# ReuseBlock_esp32_on_connector_2024-12-01.net
KiCad netlist of a schematic drawn in EasyEDA Pro
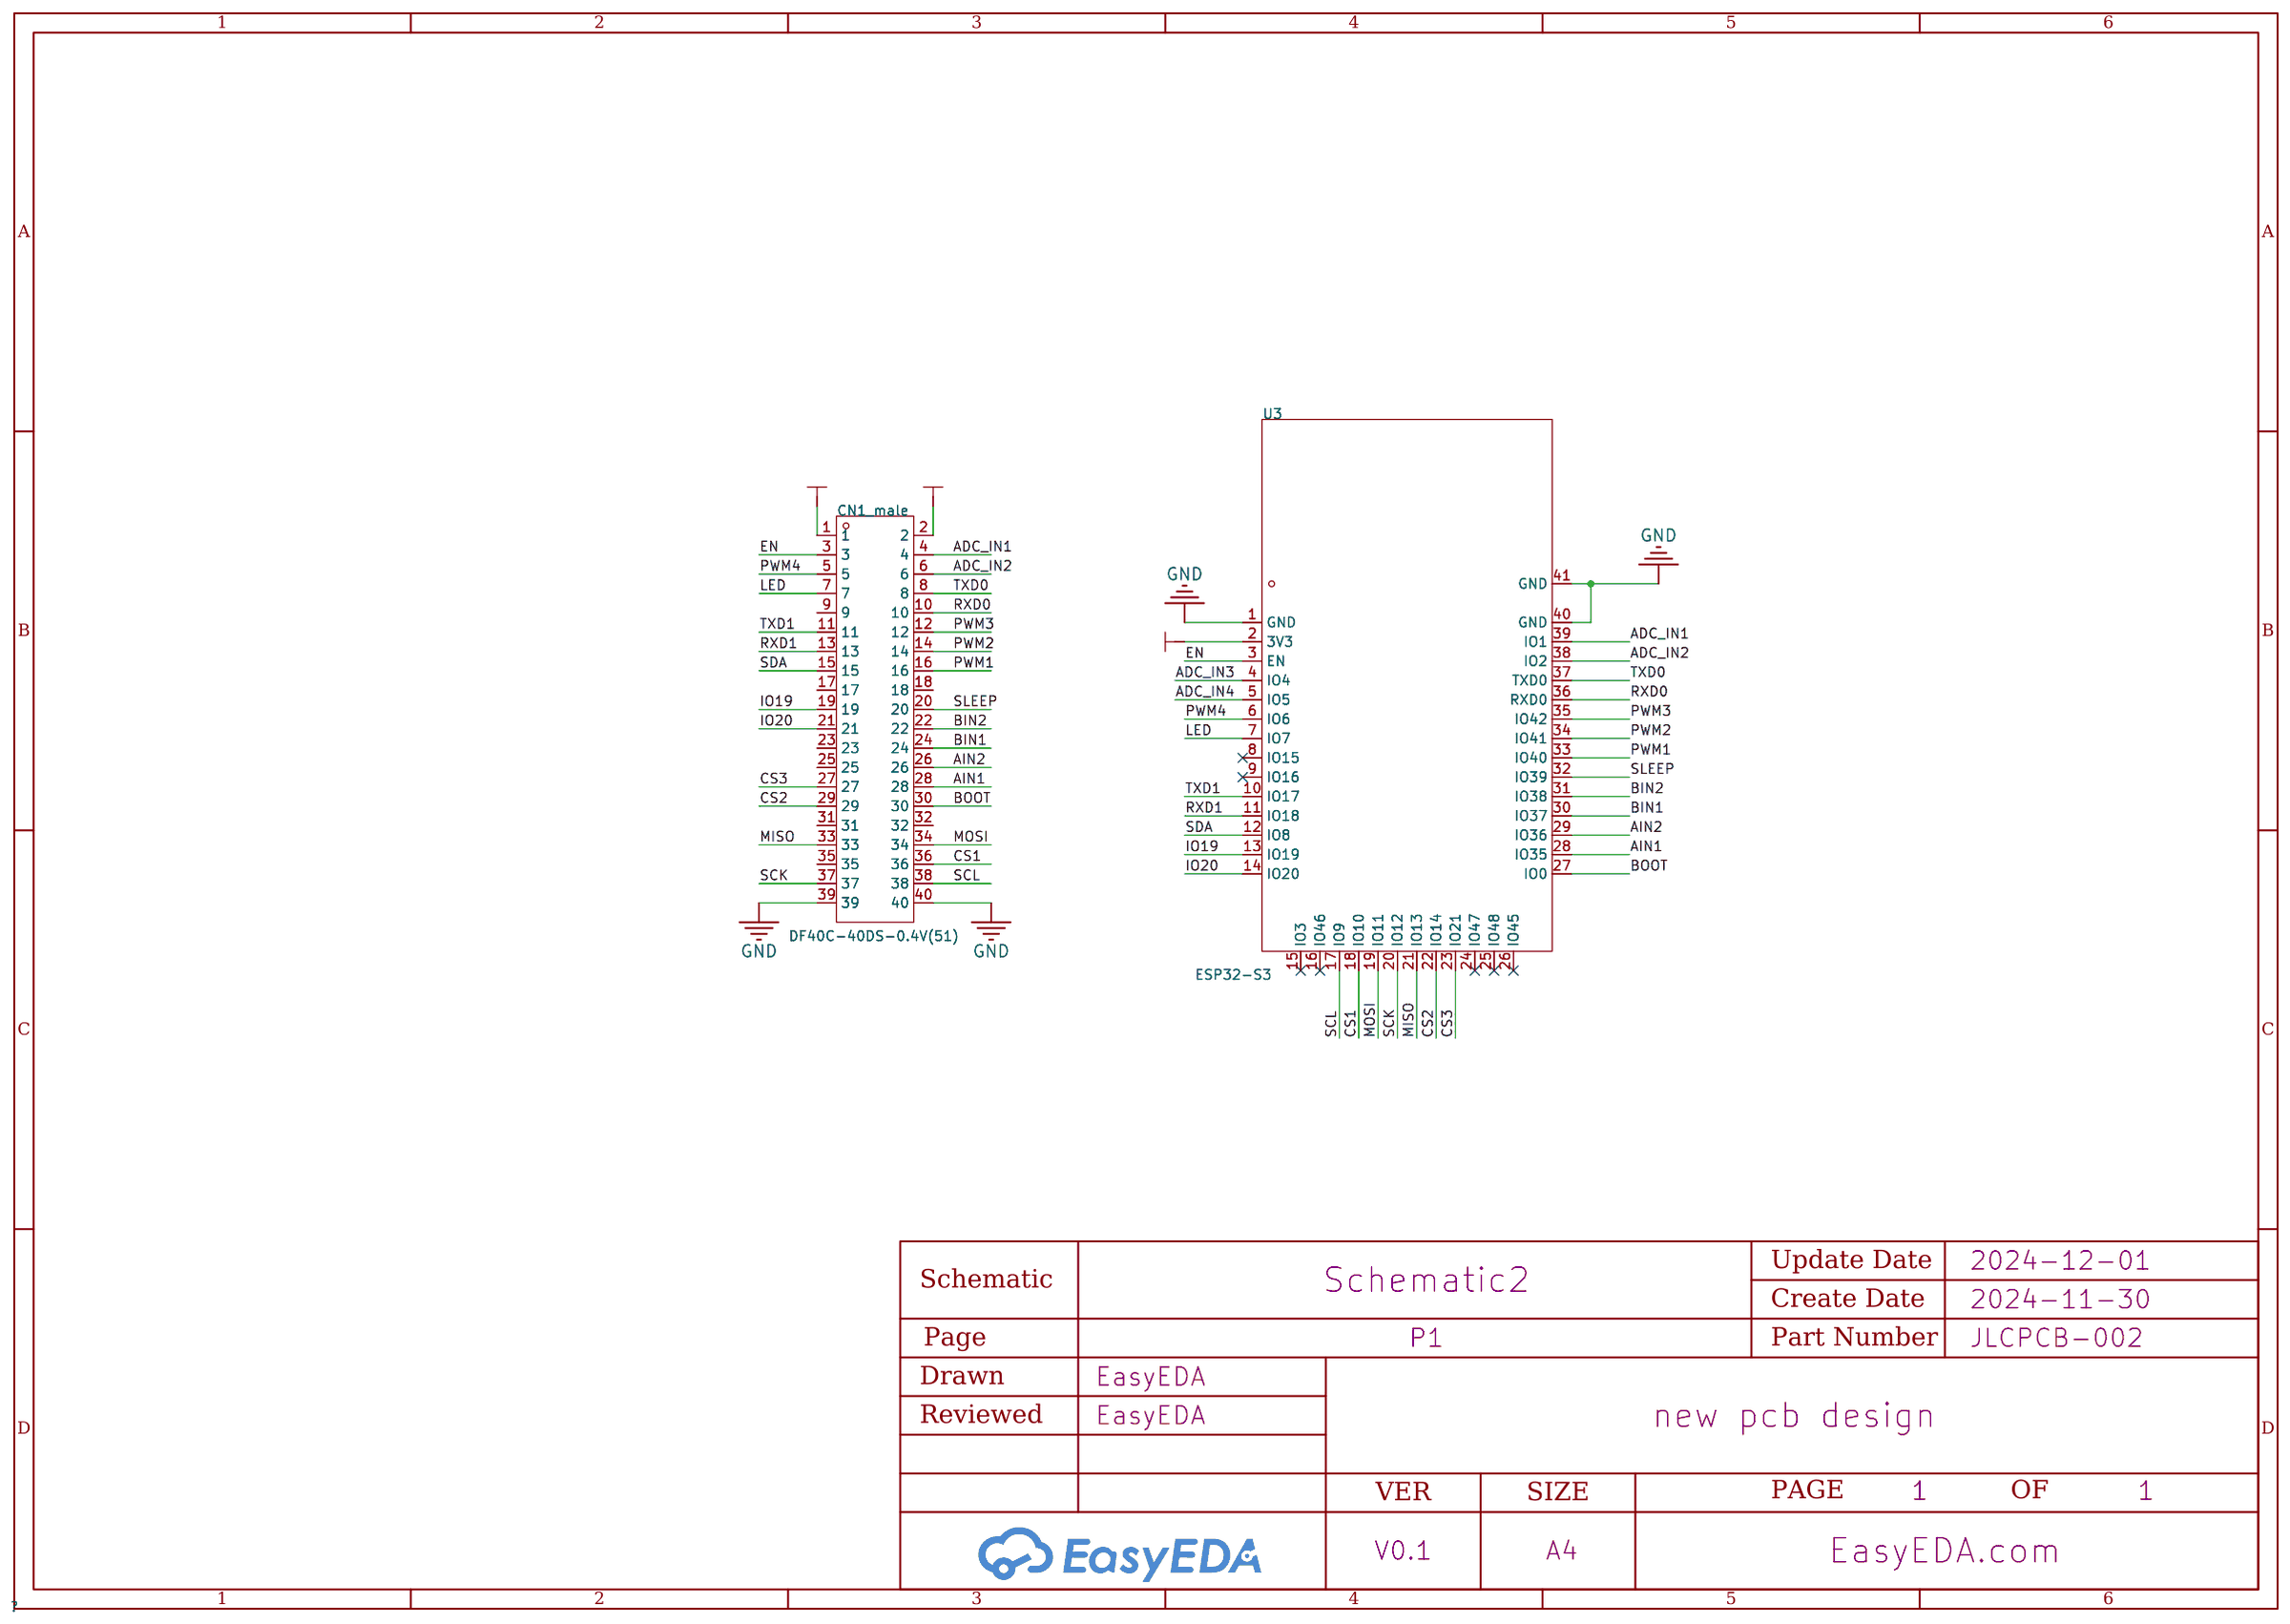
[diagram p0: schematic sheet]

(export (version "E")
  (design (tool "Eeschema 10.0.6"))
  (components
    (comp (ref "CN1_male")
      (value "DF40C-40DS-0.4V(51)")
      (footprint "easyedapro:CONN-SMD_DF40C-40DS-0.4V51")
      (fields (field (name "Manufacturer") "HRS(广濑)"))
      (libsource (lib "easyedapro") (part "DF40C-40DS-0.4V(51)"))
    )
    (comp (ref "U3")
      (value "ESP32-S3")
      (footprint "easyedapro:WIRELM-SMD_ESP32-S3-WROOM-1")
      (description "Core Processor:ESP32-S3 Chip Support Interface:I2C；GPIO；SPI；PWM；ADC；UART；USB；I2S Frequency:2.4GHz")
      (fields
        (field (name "Manufacturer Part") "ESP32-S3-WROOM-1-N8R2")
        (field (name "Manufacturer") "ESPRESSIF(乐鑫)")
      )
      (libsource (lib "easyedapro") (part "ESP32-S3-WROOM-1(N8R2)"))
    )
  )
  (nets
    (net (code "1") (name "/ADC_IN1") (class "Default")
      (node (ref "CN1_male") (pin "4") (pinfunction "4_4") (pintype "unspecified"))
      (node (ref "U3") (pin "39") (pinfunction "IO1_39") (pintype "unspecified"))
    )
    (net (code "2") (name "/ADC_IN2") (class "Default")
      (node (ref "CN1_male") (pin "6") (pinfunction "6_6") (pintype "unspecified"))
      (node (ref "U3") (pin "38") (pinfunction "IO2_38") (pintype "unspecified"))
    )
    (net (code "3") (name "/ADC_IN3") (class "Default")
      (node (ref "U3") (pin "4") (pinfunction "IO4_4") (pintype "unspecified"))
    )
    (net (code "4") (name "/ADC_IN4") (class "Default")
      (node (ref "U3") (pin "5") (pinfunction "IO5_5") (pintype "unspecified"))
    )
    (net (code "5") (name "/AIN1") (class "Default")
      (node (ref "CN1_male") (pin "28") (pinfunction "28_28") (pintype "unspecified"))
      (node (ref "U3") (pin "28") (pinfunction "IO35_28") (pintype "unspecified"))
    )
    (net (code "6") (name "/AIN2") (class "Default")
      (node (ref "CN1_male") (pin "26") (pinfunction "26_26") (pintype "unspecified"))
      (node (ref "U3") (pin "29") (pinfunction "IO36_29") (pintype "unspecified"))
    )
    (net (code "7") (name "/BIN1") (class "Default")
      (node (ref "CN1_male") (pin "24") (pinfunction "24_24") (pintype "unspecified"))
      (node (ref "U3") (pin "30") (pinfunction "IO37_30") (pintype "unspecified"))
    )
    (net (code "8") (name "/BIN2") (class "Default")
      (node (ref "CN1_male") (pin "22") (pinfunction "22_22") (pintype "unspecified"))
      (node (ref "U3") (pin "31") (pinfunction "IO38_31") (pintype "unspecified"))
    )
    (net (code "9") (name "/BOOT") (class "Default")
      (node (ref "CN1_male") (pin "30") (pinfunction "30_30") (pintype "unspecified"))
      (node (ref "U3") (pin "27") (pinfunction "IO0_27") (pintype "unspecified"))
    )
    (net (code "10") (name "/CS1") (class "Default")
      (node (ref "CN1_male") (pin "36") (pinfunction "36_36") (pintype "unspecified"))
      (node (ref "U3") (pin "18") (pinfunction "IO10_18") (pintype "unspecified"))
    )
    (net (code "11") (name "/CS2") (class "Default")
      (node (ref "CN1_male") (pin "29") (pinfunction "29_29") (pintype "unspecified"))
      (node (ref "U3") (pin "22") (pinfunction "IO14_22") (pintype "unspecified"))
    )
    (net (code "12") (name "/CS3") (class "Default")
      (node (ref "CN1_male") (pin "27") (pinfunction "27_27") (pintype "unspecified"))
      (node (ref "U3") (pin "23") (pinfunction "IO21_23") (pintype "unspecified"))
    )
    (net (code "13") (name "/EN") (class "Default")
      (node (ref "CN1_male") (pin "3") (pinfunction "3_3") (pintype "unspecified"))
      (node (ref "U3") (pin "3") (pinfunction "EN_3") (pintype "unspecified"))
    )
    (net (code "14") (name "/IO19") (class "Default")
      (node (ref "CN1_male") (pin "19") (pinfunction "19_19") (pintype "unspecified"))
      (node (ref "U3") (pin "13") (pinfunction "IO19_13") (pintype "unspecified"))
    )
    (net (code "15") (name "/IO20") (class "Default")
      (node (ref "CN1_male") (pin "21") (pinfunction "21_21") (pintype "unspecified"))
      (node (ref "U3") (pin "14") (pinfunction "IO20_14") (pintype "unspecified"))
    )
    (net (code "16") (name "/LED") (class "Default")
      (node (ref "CN1_male") (pin "7") (pinfunction "7_7") (pintype "unspecified"))
      (node (ref "U3") (pin "7") (pinfunction "IO7_7") (pintype "unspecified"))
    )
    (net (code "17") (name "/MISO") (class "Default")
      (node (ref "CN1_male") (pin "33") (pinfunction "33_33") (pintype "unspecified"))
      (node (ref "U3") (pin "21") (pinfunction "IO13_21") (pintype "unspecified"))
    )
    (net (code "18") (name "/MOSI") (class "Default")
      (node (ref "CN1_male") (pin "34") (pinfunction "34_34") (pintype "unspecified"))
      (node (ref "U3") (pin "19") (pinfunction "IO11_19") (pintype "unspecified"))
    )
    (net (code "19") (name "/PWM1") (class "Default")
      (node (ref "CN1_male") (pin "16") (pinfunction "16_16") (pintype "unspecified"))
      (node (ref "U3") (pin "33") (pinfunction "IO40_33") (pintype "unspecified"))
    )
    (net (code "20") (name "/PWM2") (class "Default")
      (node (ref "CN1_male") (pin "14") (pinfunction "14_14") (pintype "unspecified"))
      (node (ref "U3") (pin "34") (pinfunction "IO41_34") (pintype "unspecified"))
    )
    (net (code "21") (name "/PWM3") (class "Default")
      (node (ref "CN1_male") (pin "12") (pinfunction "12_12") (pintype "unspecified"))
      (node (ref "U3") (pin "35") (pinfunction "IO42_35") (pintype "unspecified"))
    )
    (net (code "22") (name "/PWM4") (class "Default")
      (node (ref "CN1_male") (pin "5") (pinfunction "5_5") (pintype "unspecified"))
      (node (ref "U3") (pin "6") (pinfunction "IO6_6") (pintype "unspecified"))
    )
    (net (code "23") (name "/RXD0") (class "Default")
      (node (ref "CN1_male") (pin "10") (pinfunction "10_10") (pintype "unspecified"))
      (node (ref "U3") (pin "36") (pinfunction "RXD0_36") (pintype "unspecified"))
    )
    (net (code "24") (name "/RXD1") (class "Default")
      (node (ref "CN1_male") (pin "13") (pinfunction "13_13") (pintype "unspecified"))
      (node (ref "U3") (pin "11") (pinfunction "IO18_11") (pintype "unspecified"))
    )
    (net (code "25") (name "/SCK") (class "Default")
      (node (ref "CN1_male") (pin "37") (pinfunction "37_37") (pintype "unspecified"))
      (node (ref "U3") (pin "20") (pinfunction "IO12_20") (pintype "unspecified"))
    )
    (net (code "26") (name "/SCL") (class "Default")
      (node (ref "CN1_male") (pin "38") (pinfunction "38_38") (pintype "unspecified"))
      (node (ref "U3") (pin "17") (pinfunction "IO9_17") (pintype "unspecified"))
    )
    (net (code "27") (name "/SDA") (class "Default")
      (node (ref "CN1_male") (pin "15") (pinfunction "15_15") (pintype "unspecified"))
      (node (ref "U3") (pin "12") (pinfunction "IO8_12") (pintype "unspecified"))
    )
    (net (code "28") (name "/SLEEP") (class "Default")
      (node (ref "CN1_male") (pin "20") (pinfunction "20_20") (pintype "unspecified"))
      (node (ref "U3") (pin "32") (pinfunction "IO39_32") (pintype "unspecified"))
    )
    (net (code "29") (name "/TXD0") (class "Default")
      (node (ref "CN1_male") (pin "8") (pinfunction "8_8") (pintype "unspecified"))
      (node (ref "U3") (pin "37") (pinfunction "TXD0_37") (pintype "unspecified"))
    )
    (net (code "30") (name "/TXD1") (class "Default")
      (node (ref "CN1_male") (pin "11") (pinfunction "11_11") (pintype "unspecified"))
      (node (ref "U3") (pin "10") (pinfunction "IO17_10") (pintype "unspecified"))
    )
    (net (code "31") (name "GND") (class "Default")
      (node (ref "CN1_male") (pin "39") (pinfunction "39_39") (pintype "unspecified"))
      (node (ref "CN1_male") (pin "40") (pinfunction "40_40") (pintype "unspecified"))
      (node (ref "U3") (pin "1") (pinfunction "GND_1") (pintype "unspecified"))
      (node (ref "U3") (pin "40") (pinfunction "GND_40") (pintype "unspecified"))
      (node (ref "U3") (pin "41") (pinfunction "GND_41") (pintype "unspecified"))
    )
    (net (code "32") (name "VCC_3V3") (class "Default")
      (node (ref "CN1_male") (pin "1") (pinfunction "1_1") (pintype "unspecified"))
      (node (ref "CN1_male") (pin "2") (pinfunction "2_2") (pintype "unspecified"))
      (node (ref "U3") (pin "2") (pinfunction "3V3_2") (pintype "unspecified"))
    )
    (net (code "33") (name "unconnected-(CN1_male-Pad9)") (class "Default")
      (node (ref "CN1_male") (pin "9") (pinfunction "9_9") (pintype "unspecified"))
    )
    (net (code "34") (name "unconnected-(CN1_male-Pad17)") (class "Default")
      (node (ref "CN1_male") (pin "17") (pinfunction "17_17") (pintype "unspecified"))
    )
    (net (code "35") (name "unconnected-(CN1_male-Pad18)") (class "Default")
      (node (ref "CN1_male") (pin "18") (pinfunction "18_18") (pintype "unspecified"))
    )
    (net (code "36") (name "unconnected-(CN1_male-Pad23)") (class "Default")
      (node (ref "CN1_male") (pin "23") (pinfunction "23_23") (pintype "unspecified"))
    )
    (net (code "37") (name "unconnected-(CN1_male-Pad25)") (class "Default")
      (node (ref "CN1_male") (pin "25") (pinfunction "25_25") (pintype "unspecified"))
    )
    (net (code "38") (name "unconnected-(CN1_male-Pad31)") (class "Default")
      (node (ref "CN1_male") (pin "31") (pinfunction "31_31") (pintype "unspecified"))
    )
    (net (code "39") (name "unconnected-(CN1_male-Pad32)") (class "Default")
      (node (ref "CN1_male") (pin "32") (pinfunction "32_32") (pintype "unspecified"))
    )
    (net (code "40") (name "unconnected-(CN1_male-Pad35)") (class "Default")
      (node (ref "CN1_male") (pin "35") (pinfunction "35_35") (pintype "unspecified"))
    )
    (net (code "41") (name "unconnected-(U3-IO3-Pad15)") (class "Default")
      (node (ref "U3") (pin "15") (pinfunction "IO3_15") (pintype "unspecified+no_connect"))
    )
    (net (code "42") (name "unconnected-(U3-IO15-Pad8)") (class "Default")
      (node (ref "U3") (pin "8") (pinfunction "IO15_8") (pintype "unspecified+no_connect"))
    )
    (net (code "43") (name "unconnected-(U3-IO16-Pad9)") (class "Default")
      (node (ref "U3") (pin "9") (pinfunction "IO16_9") (pintype "unspecified+no_connect"))
    )
    (net (code "44") (name "unconnected-(U3-IO45-Pad26)") (class "Default")
      (node (ref "U3") (pin "26") (pinfunction "IO45_26") (pintype "unspecified+no_connect"))
    )
    (net (code "45") (name "unconnected-(U3-IO46-Pad16)") (class "Default")
      (node (ref "U3") (pin "16") (pinfunction "IO46_16") (pintype "unspecified+no_connect"))
    )
    (net (code "46") (name "unconnected-(U3-IO47-Pad24)") (class "Default")
      (node (ref "U3") (pin "24") (pinfunction "IO47_24") (pintype "unspecified+no_connect"))
    )
    (net (code "47") (name "unconnected-(U3-IO48-Pad25)") (class "Default")
      (node (ref "U3") (pin "25") (pinfunction "IO48_25") (pintype "unspecified+no_connect"))
    )
  )
)
